# Stepper_Motor.net
KiCad netlist of a schematic drawn in Altium Designer
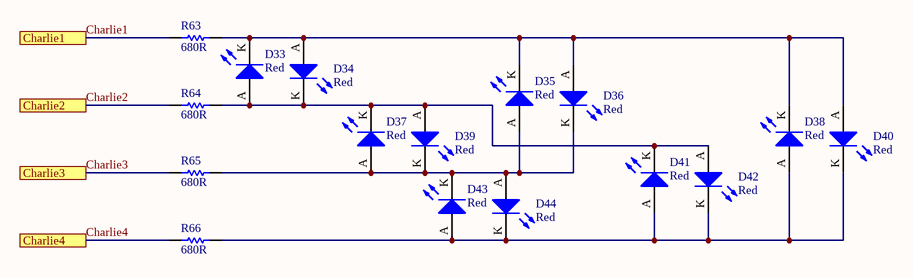
[diagram p0: Stepper Motor.SchDoc]

(export (version "E")
  (design (tool "Eeschema 10.0.6"))
  (components
    (comp (ref "D33")
      (value "Red")
      (footprint "0805 LED")
      (description "Red LED Indication - Discrete 1.75V 0805 (2012 Metric)")
      (fields (field (name "MANUFACTURER") "ROHM Semiconductor") (field (name "PART NUMBER") "SML-210LTT86"))
      (libsource (lib "ts_19-standard-library") (part "LED"))
    )
    (comp (ref "D34")
      (value "Red")
      (footprint "0805 LED")
      (description "Red LED Indication - Discrete 1.75V 0805 (2012 Metric)")
      (fields (field (name "MANUFACTURER") "ROHM Semiconductor") (field (name "PART NUMBER") "SML-210LTT86"))
      (libsource (lib "ts_19-standard-library") (part "LED"))
    )
    (comp (ref "D35")
      (value "Red")
      (footprint "0805 LED")
      (description "Red LED Indication - Discrete 1.75V 0805 (2012 Metric)")
      (fields (field (name "MANUFACTURER") "ROHM Semiconductor") (field (name "PART NUMBER") "SML-210LTT86"))
      (libsource (lib "ts_19-standard-library") (part "LED"))
    )
    (comp (ref "D36")
      (value "Red")
      (footprint "0805 LED")
      (description "Red LED Indication - Discrete 1.75V 0805 (2012 Metric)")
      (fields (field (name "MANUFACTURER") "ROHM Semiconductor") (field (name "PART NUMBER") "SML-210LTT86"))
      (libsource (lib "ts_19-standard-library") (part "LED"))
    )
    (comp (ref "D37")
      (value "Red")
      (footprint "0805 LED")
      (description "Red LED Indication - Discrete 1.75V 0805 (2012 Metric)")
      (fields (field (name "MANUFACTURER") "ROHM Semiconductor") (field (name "PART NUMBER") "SML-210LTT86"))
      (libsource (lib "ts_19-standard-library") (part "LED"))
    )
    (comp (ref "D38")
      (value "Red")
      (footprint "0805 LED")
      (description "Red LED Indication - Discrete 1.75V 0805 (2012 Metric)")
      (fields (field (name "MANUFACTURER") "ROHM Semiconductor") (field (name "PART NUMBER") "SML-210LTT86"))
      (libsource (lib "ts_19-standard-library") (part "LED"))
    )
    (comp (ref "D39")
      (value "Red")
      (footprint "0805 LED")
      (description "Red LED Indication - Discrete 1.75V 0805 (2012 Metric)")
      (fields (field (name "MANUFACTURER") "ROHM Semiconductor") (field (name "PART NUMBER") "SML-210LTT86"))
      (libsource (lib "ts_19-standard-library") (part "LED"))
    )
    (comp (ref "D40")
      (value "Red")
      (footprint "0805 LED")
      (description "Red LED Indication - Discrete 1.75V 0805 (2012 Metric)")
      (fields (field (name "MANUFACTURER") "ROHM Semiconductor") (field (name "PART NUMBER") "SML-210LTT86"))
      (libsource (lib "ts_19-standard-library") (part "LED"))
    )
    (comp (ref "D41")
      (value "Red")
      (footprint "0805 LED")
      (description "Red LED Indication - Discrete 1.75V 0805 (2012 Metric)")
      (fields (field (name "MANUFACTURER") "ROHM Semiconductor") (field (name "PART NUMBER") "SML-210LTT86"))
      (libsource (lib "ts_19-standard-library") (part "LED"))
    )
    (comp (ref "D42")
      (value "Red")
      (footprint "0805 LED")
      (description "Red LED Indication - Discrete 1.75V 0805 (2012 Metric)")
      (fields (field (name "MANUFACTURER") "ROHM Semiconductor") (field (name "PART NUMBER") "SML-210LTT86"))
      (libsource (lib "ts_19-standard-library") (part "LED"))
    )
    (comp (ref "D43")
      (value "Red")
      (footprint "0805 LED")
      (description "Red LED Indication - Discrete 1.75V 0805 (2012 Metric)")
      (fields (field (name "MANUFACTURER") "ROHM Semiconductor") (field (name "PART NUMBER") "SML-210LTT86"))
      (libsource (lib "ts_19-standard-library") (part "LED"))
    )
    (comp (ref "D44")
      (value "Red")
      (footprint "0805 LED")
      (description "Red LED Indication - Discrete 1.75V 0805 (2012 Metric)")
      (fields (field (name "MANUFACTURER") "ROHM Semiconductor") (field (name "PART NUMBER") "SML-210LTT86"))
      (libsource (lib "ts_19-standard-library") (part "LED"))
    )
    (comp (ref "R63")
      (value "680R")
      (footprint "0805")
      (fields
        (field (name "MANUFACTURER") "YAGEO")
        (field (name "PART NUMBER") "RC0805FR07680RL")
        (field (name "TOLERANCE") "0.01")
      )
      (libsource (lib "ts_19-standard-library") (part "Resistor"))
    )
    (comp (ref "R64")
      (value "680R")
      (footprint "0805")
      (fields
        (field (name "MANUFACTURER") "YAGEO")
        (field (name "PART NUMBER") "RC0805FR07680RL")
        (field (name "TOLERANCE") "0.01")
      )
      (libsource (lib "ts_19-standard-library") (part "Resistor"))
    )
    (comp (ref "R65")
      (value "680R")
      (footprint "0805")
      (fields
        (field (name "MANUFACTURER") "YAGEO")
        (field (name "PART NUMBER") "RC0805FR07680RL")
        (field (name "TOLERANCE") "0.01")
      )
      (libsource (lib "ts_19-standard-library") (part "Resistor"))
    )
    (comp (ref "R66")
      (value "680R")
      (footprint "0805")
      (fields
        (field (name "MANUFACTURER") "YAGEO")
        (field (name "PART NUMBER") "RC0805FR07680RL")
        (field (name "TOLERANCE") "0.01")
      )
      (libsource (lib "ts_19-standard-library") (part "Resistor"))
    )
  )
  (nets
    (net (code "1") (name "/Charlie1") (class "Default")
      (node (ref "R63") (pin "2") (pinfunction "2_2") (pintype "passive"))
    )
    (net (code "2") (name "/Charlie2") (class "Default")
      (node (ref "R64") (pin "2") (pinfunction "2_2") (pintype "passive"))
    )
    (net (code "3") (name "/Charlie3") (class "Default")
      (node (ref "R65") (pin "2") (pinfunction "2_2") (pintype "passive"))
    )
    (net (code "4") (name "/Charlie4") (class "Default")
      (node (ref "R66") (pin "2") (pinfunction "2_2") (pintype "passive"))
    )
    (net (code "5") (name "Net-(D33-PadA)") (class "Default")
      (node (ref "D33") (pin "A") (pinfunction "A_A") (pintype "passive"))
      (node (ref "D34") (pin "K") (pinfunction "K_K") (pintype "passive"))
      (node (ref "D37") (pin "K") (pinfunction "K_K") (pintype "passive"))
      (node (ref "D39") (pin "A") (pinfunction "A_A") (pintype "passive"))
      (node (ref "D41") (pin "K") (pinfunction "K_K") (pintype "passive"))
      (node (ref "D42") (pin "A") (pinfunction "A_A") (pintype "passive"))
      (node (ref "R64") (pin "1") (pinfunction "1_1") (pintype "passive"))
    )
    (net (code "6") (name "Net-(D33-PadK)") (class "Default")
      (node (ref "D33") (pin "K") (pinfunction "K_K") (pintype "passive"))
      (node (ref "D34") (pin "A") (pinfunction "A_A") (pintype "passive"))
      (node (ref "D35") (pin "K") (pinfunction "K_K") (pintype "passive"))
      (node (ref "D36") (pin "A") (pinfunction "A_A") (pintype "passive"))
      (node (ref "D38") (pin "K") (pinfunction "K_K") (pintype "passive"))
      (node (ref "D40") (pin "A") (pinfunction "A_A") (pintype "passive"))
      (node (ref "R63") (pin "1") (pinfunction "1_1") (pintype "passive"))
    )
    (net (code "7") (name "Net-(D35-PadA)") (class "Default")
      (node (ref "D35") (pin "A") (pinfunction "A_A") (pintype "passive"))
      (node (ref "D36") (pin "K") (pinfunction "K_K") (pintype "passive"))
      (node (ref "D37") (pin "A") (pinfunction "A_A") (pintype "passive"))
      (node (ref "D39") (pin "K") (pinfunction "K_K") (pintype "passive"))
      (node (ref "D43") (pin "K") (pinfunction "K_K") (pintype "passive"))
      (node (ref "D44") (pin "A") (pinfunction "A_A") (pintype "passive"))
      (node (ref "R65") (pin "1") (pinfunction "1_1") (pintype "passive"))
    )
    (net (code "8") (name "Net-(D38-PadA)") (class "Default")
      (node (ref "D38") (pin "A") (pinfunction "A_A") (pintype "passive"))
      (node (ref "D40") (pin "K") (pinfunction "K_K") (pintype "passive"))
      (node (ref "D41") (pin "A") (pinfunction "A_A") (pintype "passive"))
      (node (ref "D42") (pin "K") (pinfunction "K_K") (pintype "passive"))
      (node (ref "D43") (pin "A") (pinfunction "A_A") (pintype "passive"))
      (node (ref "D44") (pin "K") (pinfunction "K_K") (pintype "passive"))
      (node (ref "R66") (pin "1") (pinfunction "1_1") (pintype "passive"))
    )
  )
)
